# inclinometer-breakout-SCA100T.net
KiCad netlist of a schematic drawn in EAGLE
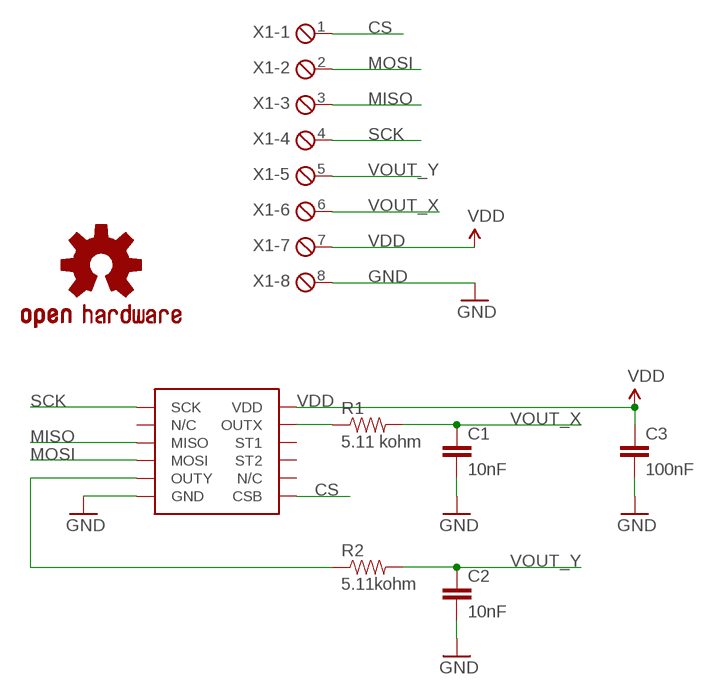
[diagram p0: schematic, sheet 1]

(export (version "E")
  (design (tool "Eeschema 10.0.6"))
  (components
    (comp (ref "C1")
      (value "10nF")
      (footprint "eagle-import:0603-CAP")
      (libsource (lib "eagle-import") (part "CAP0603-CAP"))
    )
    (comp (ref "C2")
      (value "10nF")
      (footprint "eagle-import:0603-CAP")
      (libsource (lib "eagle-import") (part "CAP0603-CAP"))
    )
    (comp (ref "C3")
      (value "100nF")
      (footprint "eagle-import:0603-CAP")
      (libsource (lib "eagle-import") (part "CAP0603-CAP"))
    )
    (comp (ref "LOGO1")
      (value "OSHW-LOGOM")
      (footprint "eagle-import:OSHW-LOGO-M")
      (libsource (lib "eagle-import") (part "OSHW-LOGOM"))
    )
    (comp (ref "R1")
      (value "5.11 kohm")
      (footprint "eagle-import:0603-RES")
      (libsource (lib "eagle-import") (part "RESISTOR0603-RES"))
    )
    (comp (ref "R2")
      (value "5.11kohm")
      (footprint "eagle-import:0603-RES")
      (libsource (lib "eagle-import") (part "RESISTOR0603-RES"))
    )
    (comp (ref "U$1")
      (value "SCA100T")
      (footprint "eagle-import:SCA1000")
      (libsource (lib "eagle-import") (part "SCA1000"))
    )
    (comp (ref "X1")
      (value "MPT8")
      (footprint "eagle-import:8POL254")
      (libsource (lib "eagle-import") (part "MPT8"))
    )
  )
  (nets
    (net (code "1") (name "/CS") (class "Default")
      (node (ref "U$1") (pin "7") (pinfunction "CSB_7") (pintype "bidirectional"))
      (node (ref "X1") (pin "1") (pinfunction "1_1") (pintype "passive"))
    )
    (net (code "2") (name "/MISO") (class "Default")
      (node (ref "U$1") (pin "3") (pinfunction "MISO_3") (pintype "bidirectional"))
      (node (ref "X1") (pin "3") (pinfunction "1_3") (pintype "passive"))
    )
    (net (code "3") (name "/MOSI") (class "Default")
      (node (ref "U$1") (pin "4") (pinfunction "MOSI_4") (pintype "bidirectional"))
      (node (ref "X1") (pin "2") (pinfunction "1_2") (pintype "passive"))
    )
    (net (code "4") (name "/SCK") (class "Default")
      (node (ref "U$1") (pin "1") (pinfunction "SCK_1") (pintype "bidirectional"))
      (node (ref "X1") (pin "4") (pinfunction "1_4") (pintype "passive"))
    )
    (net (code "5") (name "/VOUT_X") (class "Default")
      (node (ref "C1") (pin "1") (pinfunction "1_1") (pintype "passive"))
      (node (ref "R1") (pin "2") (pinfunction "2_2") (pintype "passive"))
      (node (ref "X1") (pin "6") (pinfunction "1_6") (pintype "passive"))
    )
    (net (code "6") (name "/VOUT_Y") (class "Default")
      (node (ref "C2") (pin "1") (pinfunction "1_1") (pintype "passive"))
      (node (ref "R2") (pin "2") (pinfunction "2_2") (pintype "passive"))
      (node (ref "X1") (pin "5") (pinfunction "1_5") (pintype "passive"))
    )
    (net (code "7") (name "GND") (class "Default")
      (node (ref "C1") (pin "2") (pinfunction "2_2") (pintype "passive"))
      (node (ref "C2") (pin "2") (pinfunction "2_2") (pintype "passive"))
      (node (ref "C3") (pin "2") (pinfunction "2_2") (pintype "passive"))
      (node (ref "U$1") (pin "6") (pinfunction "GND_6") (pintype "bidirectional"))
      (node (ref "X1") (pin "8") (pinfunction "1_8") (pintype "passive"))
    )
    (net (code "8") (name "Net-(U$1-OUTX)") (class "Default")
      (node (ref "R1") (pin "1") (pinfunction "1_1") (pintype "passive"))
      (node (ref "U$1") (pin "11") (pinfunction "OUTX_11") (pintype "bidirectional"))
    )
    (net (code "9") (name "Net-(U$1-OUTY)") (class "Default")
      (node (ref "R2") (pin "1") (pinfunction "1_1") (pintype "passive"))
      (node (ref "U$1") (pin "5") (pinfunction "OUTY_5") (pintype "bidirectional"))
    )
    (net (code "10") (name "VDD") (class "Default")
      (node (ref "C3") (pin "1") (pinfunction "1_1") (pintype "passive"))
      (node (ref "U$1") (pin "12") (pinfunction "VDD_12") (pintype "bidirectional"))
      (node (ref "X1") (pin "7") (pinfunction "1_7") (pintype "passive"))
    )
    (net (code "11") (name "unconnected-(U$1-N{slash}C-Pad2)") (class "Default")
      (node (ref "U$1") (pin "2") (pinfunction "N/C_2") (pintype "bidirectional"))
    )
    (net (code "12") (name "unconnected-(U$1-N{slash}C-Pad8)") (class "Default")
      (node (ref "U$1") (pin "8") (pinfunction "N/C_8") (pintype "bidirectional"))
    )
    (net (code "13") (name "unconnected-(U$1-ST1-Pad10)") (class "Default")
      (node (ref "U$1") (pin "10") (pinfunction "ST1_10") (pintype "bidirectional"))
    )
    (net (code "14") (name "unconnected-(U$1-ST2-Pad9)") (class "Default")
      (node (ref "U$1") (pin "9") (pinfunction "ST2_9") (pintype "bidirectional"))
    )
  )
)
